# microcontroller.net
KiCad netlist of a schematic drawn in Altium Designer
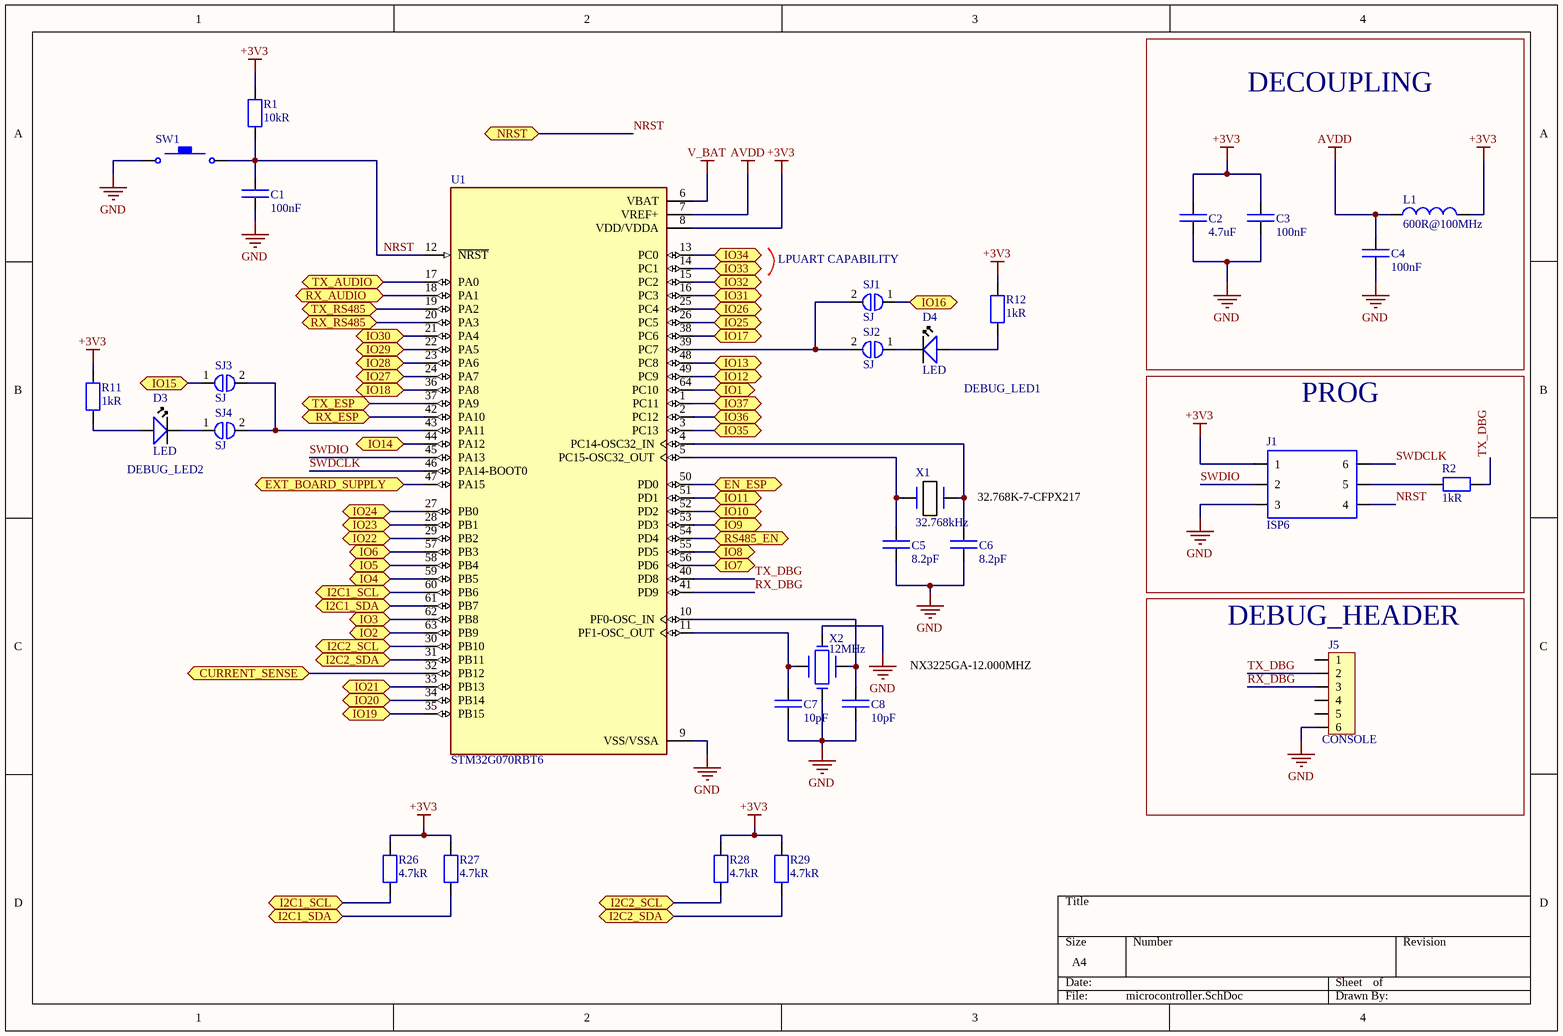
[diagram p0: microcontroller.SchDoc]

(export (version "E")
  (design (tool "Eeschema 10.0.6"))
  (components
    (comp (ref "C1") (value "100nF") (footprint "C0603") (libsource (lib "przem_lib") (part "Cap_SMD")))
    (comp (ref "C2") (value "4.7uF") (footprint "C0805") (libsource (lib "przem_lib") (part "Cap_SMD")))
    (comp (ref "C3") (value "100nF") (footprint "C0603") (libsource (lib "przem_lib") (part "Cap_SMD")))
    (comp (ref "C4") (value "100nF") (footprint "C0603") (libsource (lib "przem_lib") (part "Cap_SMD")))
    (comp (ref "C5") (value "8.2pF") (footprint "C0603") (libsource (lib "przem_lib") (part "Cap_SMD")))
    (comp (ref "C6") (value "8.2pF") (footprint "C0603") (libsource (lib "przem_lib") (part "Cap_SMD")))
    (comp (ref "C7") (value "10pF") (footprint "C0603") (libsource (lib "przem_lib") (part "Cap_SMD")))
    (comp (ref "C8") (value "10pF") (footprint "C0603") (libsource (lib "przem_lib") (part "Cap_SMD")))
    (comp (ref "D3") (value "LED") (footprint "LED0805") (libsource (lib "przem_lib") (part "LED")))
    (comp (ref "D4") (value "LED") (footprint "LED0805") (libsource (lib "przem_lib") (part "LED")))
    (comp (ref "J1") (value "ISP6") (footprint "ISP-6") (libsource (lib "przem_lib") (part "ISP6")))
    (comp (ref "J5")
      (value "CONSOLE")
      (footprint "pin_header_6_male")
      (libsource (lib "przem_lib") (part "GOLDPIN_6"))
    )
    (comp (ref "L1")
      (value "600R@100MHz")
      (footprint "R0603")
      (libsource (lib "przem_lib") (part "Inductor"))
    )
    (comp (ref "R1") (value "10kR") (footprint "R0603") (libsource (lib "przem_lib") (part "Res")))
    (comp (ref "R2") (value "1kR") (footprint "R0603") (libsource (lib "przem_lib") (part "Res")))
    (comp (ref "R11") (value "1kR") (footprint "R0603") (libsource (lib "przem_lib") (part "Res")))
    (comp (ref "R12") (value "1kR") (footprint "R0603") (libsource (lib "przem_lib") (part "Res")))
    (comp (ref "R26") (value "4.7kR") (footprint "R0805") (libsource (lib "przem_lib") (part "Res")))
    (comp (ref "R27") (value "4.7kR") (footprint "R0805") (libsource (lib "przem_lib") (part "Res")))
    (comp (ref "R28") (value "4.7kR") (footprint "R0805") (libsource (lib "przem_lib") (part "Res")))
    (comp (ref "R29") (value "4.7kR") (footprint "R0805") (libsource (lib "przem_lib") (part "Res")))
    (comp (ref "SJ1") (value "SJ") (footprint "SJ") (libsource (lib "przem_lib") (part "SJ")))
    (comp (ref "SJ2") (value "SJ") (footprint "SJ") (libsource (lib "przem_lib") (part "SJ")))
    (comp (ref "SJ3") (value "SJ") (footprint "SJ") (libsource (lib "") (part "SJ_1")))
    (comp (ref "SJ4") (value "SJ") (footprint "SJ") (libsource (lib "") (part "SJ_1")))
    (comp (ref "SW1")
      (value "tactile_switch")
      (footprint "tact_sw_3mmx4mm")
      (libsource (lib "przem_lib") (part "tactile_switch"))
    )
    (comp (ref "U1")
      (value "STM32G070RBT6")
      (footprint "STM32")
      (description "ARMÂ® CortexÂ®-M0+ STM32G0 Microcontroller IC 32-Bit 64MHz 128KB _128K x 8_ FLASH 64-LQFP _10x10_")
      (fields (field (name "MF") "STMicroelectronics"))
      (libsource (lib "przem_lib") (part "STM32G070RBT6"))
    )
    (comp (ref "X1")
      (value "32.768kHz")
      (footprint "XTAL_2PIN_3.2X1.5mm")
      (description "32.768K-7-CFPX217")
      (libsource (lib "przem_lib") (part "XTAL_2PIN"))
    )
    (comp (ref "X2")
      (value "12MHz")
      (footprint "XTAL_4PIN_3.2x2.5mm")
      (description "NX3225GA-12.000MHZ")
      (libsource (lib "przem_lib") (part "XTAL_4PIN"))
    )
  )
  (nets
    (net (code "1") (name "+3V3") (class "Default")
      (node (ref "C2") (pin "2") (pinfunction "2_2") (pintype "passive"))
      (node (ref "C3") (pin "2") (pinfunction "2_2") (pintype "passive"))
      (node (ref "J1") (pin "1") (pinfunction "1_1") (pintype "passive"))
      (node (ref "L1") (pin "2") (pinfunction "2_2") (pintype "passive"))
      (node (ref "R1") (pin "2") (pinfunction "2_2") (pintype "passive"))
      (node (ref "R11") (pin "2") (pinfunction "2_2") (pintype "passive"))
      (node (ref "R12") (pin "2") (pinfunction "2_2") (pintype "passive"))
      (node (ref "R26") (pin "2") (pinfunction "2_2") (pintype "passive"))
      (node (ref "R27") (pin "2") (pinfunction "2_2") (pintype "passive"))
      (node (ref "R28") (pin "2") (pinfunction "2_2") (pintype "passive"))
      (node (ref "R29") (pin "2") (pinfunction "2_2") (pintype "passive"))
      (node (ref "U1") (pin "8") (pinfunction "VDD/VDDA_8") (pintype "power_in"))
    )
    (net (code "2") (name "/CURRENT_SENSE") (class "Default")
      (node (ref "U1") (pin "32") (pinfunction "PB12_32") (pintype "bidirectional"))
    )
    (net (code "3") (name "/EN_ESP") (class "Default")
      (node (ref "U1") (pin "50") (pinfunction "PD0_50") (pintype "bidirectional"))
    )
    (net (code "4") (name "/EXT_BOARD_SUPPLY") (class "Default")
      (node (ref "U1") (pin "47") (pinfunction "PA15_47") (pintype "bidirectional"))
    )
    (net (code "5") (name "/I2C1_SCL") (class "Default")
      (node (ref "R26") (pin "1") (pinfunction "1_1") (pintype "passive"))
      (node (ref "U1") (pin "60") (pinfunction "PB6_60") (pintype "bidirectional"))
    )
    (net (code "6") (name "/I2C1_SDA") (class "Default")
      (node (ref "R27") (pin "1") (pinfunction "1_1") (pintype "passive"))
      (node (ref "U1") (pin "61") (pinfunction "PB7_61") (pintype "bidirectional"))
    )
    (net (code "7") (name "/I2C2_SCL") (class "Default")
      (node (ref "R28") (pin "1") (pinfunction "1_1") (pintype "passive"))
      (node (ref "U1") (pin "30") (pinfunction "PB10_30") (pintype "bidirectional"))
    )
    (net (code "8") (name "/I2C2_SDA") (class "Default")
      (node (ref "R29") (pin "1") (pinfunction "1_1") (pintype "passive"))
      (node (ref "U1") (pin "31") (pinfunction "PB11_31") (pintype "bidirectional"))
    )
    (net (code "9") (name "/IO1") (class "Default")
      (node (ref "U1") (pin "64") (pinfunction "PC10_64") (pintype "bidirectional"))
    )
    (net (code "10") (name "/IO2") (class "Default")
      (node (ref "U1") (pin "63") (pinfunction "PB9_63") (pintype "bidirectional"))
    )
    (net (code "11") (name "/IO3") (class "Default")
      (node (ref "U1") (pin "62") (pinfunction "PB8_62") (pintype "bidirectional"))
    )
    (net (code "12") (name "/IO4") (class "Default")
      (node (ref "U1") (pin "59") (pinfunction "PB5_59") (pintype "bidirectional"))
    )
    (net (code "13") (name "/IO5") (class "Default")
      (node (ref "U1") (pin "58") (pinfunction "PB4_58") (pintype "bidirectional"))
    )
    (net (code "14") (name "/IO6") (class "Default")
      (node (ref "U1") (pin "57") (pinfunction "PB3_57") (pintype "bidirectional"))
    )
    (net (code "15") (name "/IO7") (class "Default")
      (node (ref "U1") (pin "56") (pinfunction "PD6_56") (pintype "bidirectional"))
    )
    (net (code "16") (name "/IO8") (class "Default")
      (node (ref "U1") (pin "55") (pinfunction "PD5_55") (pintype "bidirectional"))
    )
    (net (code "17") (name "/IO9") (class "Default")
      (node (ref "U1") (pin "53") (pinfunction "PD3_53") (pintype "bidirectional"))
    )
    (net (code "18") (name "/IO10") (class "Default")
      (node (ref "U1") (pin "52") (pinfunction "PD2_52") (pintype "bidirectional"))
    )
    (net (code "19") (name "/IO11") (class "Default")
      (node (ref "U1") (pin "51") (pinfunction "PD1_51") (pintype "bidirectional"))
    )
    (net (code "20") (name "/IO12") (class "Default")
      (node (ref "U1") (pin "49") (pinfunction "PC9_49") (pintype "bidirectional"))
    )
    (net (code "21") (name "/IO13") (class "Default")
      (node (ref "U1") (pin "48") (pinfunction "PC8_48") (pintype "bidirectional"))
    )
    (net (code "22") (name "/IO14") (class "Default")
      (node (ref "U1") (pin "44") (pinfunction "PA12_44") (pintype "bidirectional"))
    )
    (net (code "23") (name "/IO15") (class "Default")
      (node (ref "SJ3") (pin "1") (pinfunction "1_1") (pintype "passive"))
    )
    (net (code "24") (name "/IO16") (class "Default")
      (node (ref "SJ1") (pin "1") (pinfunction "1_1") (pintype "passive"))
    )
    (net (code "25") (name "/IO17") (class "Default")
      (node (ref "U1") (pin "38") (pinfunction "PC6_38") (pintype "bidirectional"))
    )
    (net (code "26") (name "/IO18") (class "Default")
      (node (ref "U1") (pin "36") (pinfunction "PA8_36") (pintype "bidirectional"))
    )
    (net (code "27") (name "/IO19") (class "Default")
      (node (ref "U1") (pin "35") (pinfunction "PB15_35") (pintype "bidirectional"))
    )
    (net (code "28") (name "/IO20") (class "Default")
      (node (ref "U1") (pin "34") (pinfunction "PB14_34") (pintype "bidirectional"))
    )
    (net (code "29") (name "/IO21") (class "Default")
      (node (ref "U1") (pin "33") (pinfunction "PB13_33") (pintype "bidirectional"))
    )
    (net (code "30") (name "/IO22") (class "Default")
      (node (ref "U1") (pin "29") (pinfunction "PB2_29") (pintype "bidirectional"))
    )
    (net (code "31") (name "/IO23") (class "Default")
      (node (ref "U1") (pin "28") (pinfunction "PB1_28") (pintype "bidirectional"))
    )
    (net (code "32") (name "/IO24") (class "Default")
      (node (ref "U1") (pin "27") (pinfunction "PB0_27") (pintype "bidirectional"))
    )
    (net (code "33") (name "/IO25") (class "Default")
      (node (ref "U1") (pin "26") (pinfunction "PC5_26") (pintype "bidirectional"))
    )
    (net (code "34") (name "/IO26") (class "Default")
      (node (ref "U1") (pin "25") (pinfunction "PC4_25") (pintype "bidirectional"))
    )
    (net (code "35") (name "/IO27") (class "Default")
      (node (ref "U1") (pin "24") (pinfunction "PA7_24") (pintype "bidirectional"))
    )
    (net (code "36") (name "/IO28") (class "Default")
      (node (ref "U1") (pin "23") (pinfunction "PA6_23") (pintype "bidirectional"))
    )
    (net (code "37") (name "/IO29") (class "Default")
      (node (ref "U1") (pin "22") (pinfunction "PA5_22") (pintype "bidirectional"))
    )
    (net (code "38") (name "/IO30") (class "Default")
      (node (ref "U1") (pin "21") (pinfunction "PA4_21") (pintype "bidirectional"))
    )
    (net (code "39") (name "/IO31") (class "Default")
      (node (ref "U1") (pin "16") (pinfunction "PC3_16") (pintype "bidirectional"))
    )
    (net (code "40") (name "/IO32") (class "Default")
      (node (ref "U1") (pin "15") (pinfunction "PC2_15") (pintype "bidirectional"))
    )
    (net (code "41") (name "/IO33") (class "Default")
      (node (ref "U1") (pin "14") (pinfunction "PC1_14") (pintype "bidirectional"))
    )
    (net (code "42") (name "/IO34") (class "Default")
      (node (ref "U1") (pin "13") (pinfunction "PC0_13") (pintype "bidirectional"))
    )
    (net (code "43") (name "/IO35") (class "Default")
      (node (ref "U1") (pin "3") (pinfunction "PC13_3") (pintype "bidirectional"))
    )
    (net (code "44") (name "/IO36") (class "Default")
      (node (ref "U1") (pin "2") (pinfunction "PC12_2") (pintype "bidirectional"))
    )
    (net (code "45") (name "/IO37") (class "Default")
      (node (ref "U1") (pin "1") (pinfunction "PC11_1") (pintype "bidirectional"))
    )
    (net (code "46") (name "/NRST") (class "Default")
      (node (ref "C1") (pin "2") (pinfunction "2_2") (pintype "passive"))
      (node (ref "J1") (pin "4") (pinfunction "4_4") (pintype "passive"))
      (node (ref "R1") (pin "1") (pinfunction "1_1") (pintype "passive"))
      (node (ref "SW1") (pin "3") (pinfunction "3_3") (pintype "passive"))
      (node (ref "U1") (pin "12") (pinfunction "~{NRST}_12") (pintype "input"))
    )
    (net (code "47") (name "/RS485_EN") (class "Default")
      (node (ref "U1") (pin "54") (pinfunction "PD4_54") (pintype "bidirectional"))
    )
    (net (code "48") (name "/RX_AUDIO") (class "Default")
      (node (ref "U1") (pin "18") (pinfunction "PA1_18") (pintype "bidirectional"))
    )
    (net (code "49") (name "/RX_DBG") (class "Default")
      (node (ref "J5") (pin "3") (pinfunction "3_3") (pintype "passive"))
      (node (ref "U1") (pin "41") (pinfunction "PD9_41") (pintype "bidirectional"))
    )
    (net (code "50") (name "/RX_ESP") (class "Default")
      (node (ref "U1") (pin "42") (pinfunction "PA10_42") (pintype "bidirectional"))
    )
    (net (code "51") (name "/RX_RS485") (class "Default")
      (node (ref "U1") (pin "20") (pinfunction "PA3_20") (pintype "bidirectional"))
    )
    (net (code "52") (name "/SWDCLK") (class "Default")
      (node (ref "J1") (pin "6") (pinfunction "6_6") (pintype "passive"))
      (node (ref "U1") (pin "46") (pinfunction "PA14-BOOT0_46") (pintype "bidirectional"))
    )
    (net (code "53") (name "/SWDIO") (class "Default")
      (node (ref "J1") (pin "2") (pinfunction "2_2") (pintype "passive"))
      (node (ref "U1") (pin "45") (pinfunction "PA13_45") (pintype "bidirectional"))
    )
    (net (code "54") (name "/TX_AUDIO") (class "Default")
      (node (ref "U1") (pin "17") (pinfunction "PA0_17") (pintype "bidirectional"))
    )
    (net (code "55") (name "/TX_DBG") (class "Default")
      (node (ref "J5") (pin "2") (pinfunction "2_2") (pintype "passive"))
      (node (ref "R2") (pin "2") (pinfunction "2_2") (pintype "passive"))
      (node (ref "U1") (pin "40") (pinfunction "PD8_40") (pintype "bidirectional"))
    )
    (net (code "56") (name "/TX_ESP") (class "Default")
      (node (ref "U1") (pin "37") (pinfunction "PA9_37") (pintype "bidirectional"))
    )
    (net (code "57") (name "/TX_RS485") (class "Default")
      (node (ref "U1") (pin "19") (pinfunction "PA2_19") (pintype "bidirectional"))
    )
    (net (code "58") (name "AVDD") (class "Default")
      (node (ref "C4") (pin "2") (pinfunction "2_2") (pintype "passive"))
      (node (ref "L1") (pin "1") (pinfunction "1_1") (pintype "passive"))
      (node (ref "U1") (pin "7") (pinfunction "VREF+_7") (pintype "power_in"))
    )
    (net (code "59") (name "GND") (class "Default")
      (node (ref "C1") (pin "1") (pinfunction "1_1") (pintype "passive"))
      (node (ref "C2") (pin "1") (pinfunction "1_1") (pintype "passive"))
      (node (ref "C3") (pin "1") (pinfunction "1_1") (pintype "passive"))
      (node (ref "C4") (pin "1") (pinfunction "1_1") (pintype "passive"))
      (node (ref "C5") (pin "1") (pinfunction "1_1") (pintype "passive"))
      (node (ref "C6") (pin "1") (pinfunction "1_1") (pintype "passive"))
      (node (ref "C7") (pin "1") (pinfunction "1_1") (pintype "passive"))
      (node (ref "C8") (pin "1") (pinfunction "1_1") (pintype "passive"))
      (node (ref "J1") (pin "3") (pinfunction "3_3") (pintype "passive"))
      (node (ref "J5") (pin "6") (pinfunction "6_6") (pintype "passive"))
      (node (ref "SW1") (pin "1") (pinfunction "1_1") (pintype "passive"))
      (node (ref "U1") (pin "9") (pinfunction "VSS/VSSA_9") (pintype "power_in"))
      (node (ref "X2") (pin "2") (pinfunction "2_2") (pintype "power_in"))
      (node (ref "X2") (pin "4") (pinfunction "4_4") (pintype "power_in"))
    )
    (net (code "60") (name "Net-(D3-PadA)") (class "Default")
      (node (ref "D3") (pin "A") (pinfunction "A_A") (pintype "passive"))
      (node (ref "R11") (pin "1") (pinfunction "1_1") (pintype "passive"))
    )
    (net (code "61") (name "Net-(D3-PadK)") (class "Default")
      (node (ref "D3") (pin "K") (pinfunction "K_K") (pintype "passive"))
      (node (ref "SJ4") (pin "1") (pinfunction "1_1") (pintype "passive"))
    )
    (net (code "62") (name "Net-(D4-PadA)") (class "Default")
      (node (ref "D4") (pin "A") (pinfunction "A_A") (pintype "passive"))
      (node (ref "R12") (pin "1") (pinfunction "1_1") (pintype "passive"))
    )
    (net (code "63") (name "Net-(D4-PadK)") (class "Default")
      (node (ref "D4") (pin "K") (pinfunction "K_K") (pintype "passive"))
      (node (ref "SJ2") (pin "1") (pinfunction "1_1") (pintype "passive"))
    )
    (net (code "64") (name "Net-(J1-Pad5)") (class "Default")
      (node (ref "J1") (pin "5") (pinfunction "5_5") (pintype "passive"))
      (node (ref "R2") (pin "1") (pinfunction "1_1") (pintype "passive"))
    )
    (net (code "65") (name "Net-(U1-PA11)") (class "Default")
      (node (ref "SJ3") (pin "2") (pinfunction "2_2") (pintype "passive"))
      (node (ref "SJ4") (pin "2") (pinfunction "2_2") (pintype "passive"))
      (node (ref "U1") (pin "43") (pinfunction "PA11_43") (pintype "bidirectional"))
    )
    (net (code "66") (name "Net-(U1-PC7)") (class "Default")
      (node (ref "SJ1") (pin "2") (pinfunction "2_2") (pintype "passive"))
      (node (ref "SJ2") (pin "2") (pinfunction "2_2") (pintype "passive"))
      (node (ref "U1") (pin "39") (pinfunction "PC7_39") (pintype "bidirectional"))
    )
    (net (code "67") (name "Net-(U1-PC14-OSC32_IN)") (class "Default")
      (node (ref "C6") (pin "2") (pinfunction "2_2") (pintype "passive"))
      (node (ref "U1") (pin "4") (pinfunction "PC14-OSC32_IN_4") (pintype "bidirectional"))
      (node (ref "X1") (pin "2") (pinfunction "2_2") (pintype "passive"))
    )
    (net (code "68") (name "Net-(U1-PC15-OSC32_OUT)") (class "Default")
      (node (ref "C5") (pin "2") (pinfunction "2_2") (pintype "passive"))
      (node (ref "U1") (pin "5") (pinfunction "PC15-OSC32_OUT_5") (pintype "bidirectional"))
      (node (ref "X1") (pin "1") (pinfunction "1_1") (pintype "passive"))
    )
    (net (code "69") (name "Net-(U1-PF0-OSC_IN)") (class "Default")
      (node (ref "C8") (pin "2") (pinfunction "2_2") (pintype "passive"))
      (node (ref "U1") (pin "10") (pinfunction "PF0-OSC_IN_10") (pintype "bidirectional"))
      (node (ref "X2") (pin "3") (pinfunction "3_3") (pintype "passive"))
    )
    (net (code "70") (name "Net-(U1-PF1-OSC_OUT)") (class "Default")
      (node (ref "C7") (pin "2") (pinfunction "2_2") (pintype "passive"))
      (node (ref "U1") (pin "11") (pinfunction "PF1-OSC_OUT_11") (pintype "bidirectional"))
      (node (ref "X2") (pin "1") (pinfunction "1_1") (pintype "passive"))
    )
    (net (code "71") (name "V_BAT") (class "Default")
      (node (ref "U1") (pin "6") (pinfunction "VBAT_6") (pintype "power_in"))
    )
    (net (code "72") (name "unconnected-(J5-Pad1)") (class "Default")
      (node (ref "J5") (pin "1") (pinfunction "1_1") (pintype "passive"))
    )
    (net (code "73") (name "unconnected-(J5-Pad4)") (class "Default")
      (node (ref "J5") (pin "4") (pinfunction "4_4") (pintype "passive"))
    )
    (net (code "74") (name "unconnected-(J5-Pad5)") (class "Default")
      (node (ref "J5") (pin "5") (pinfunction "5_5") (pintype "passive"))
    )
  )
)
